# Input_Protection.net
KiCad netlist of a schematic drawn in Altium Designer
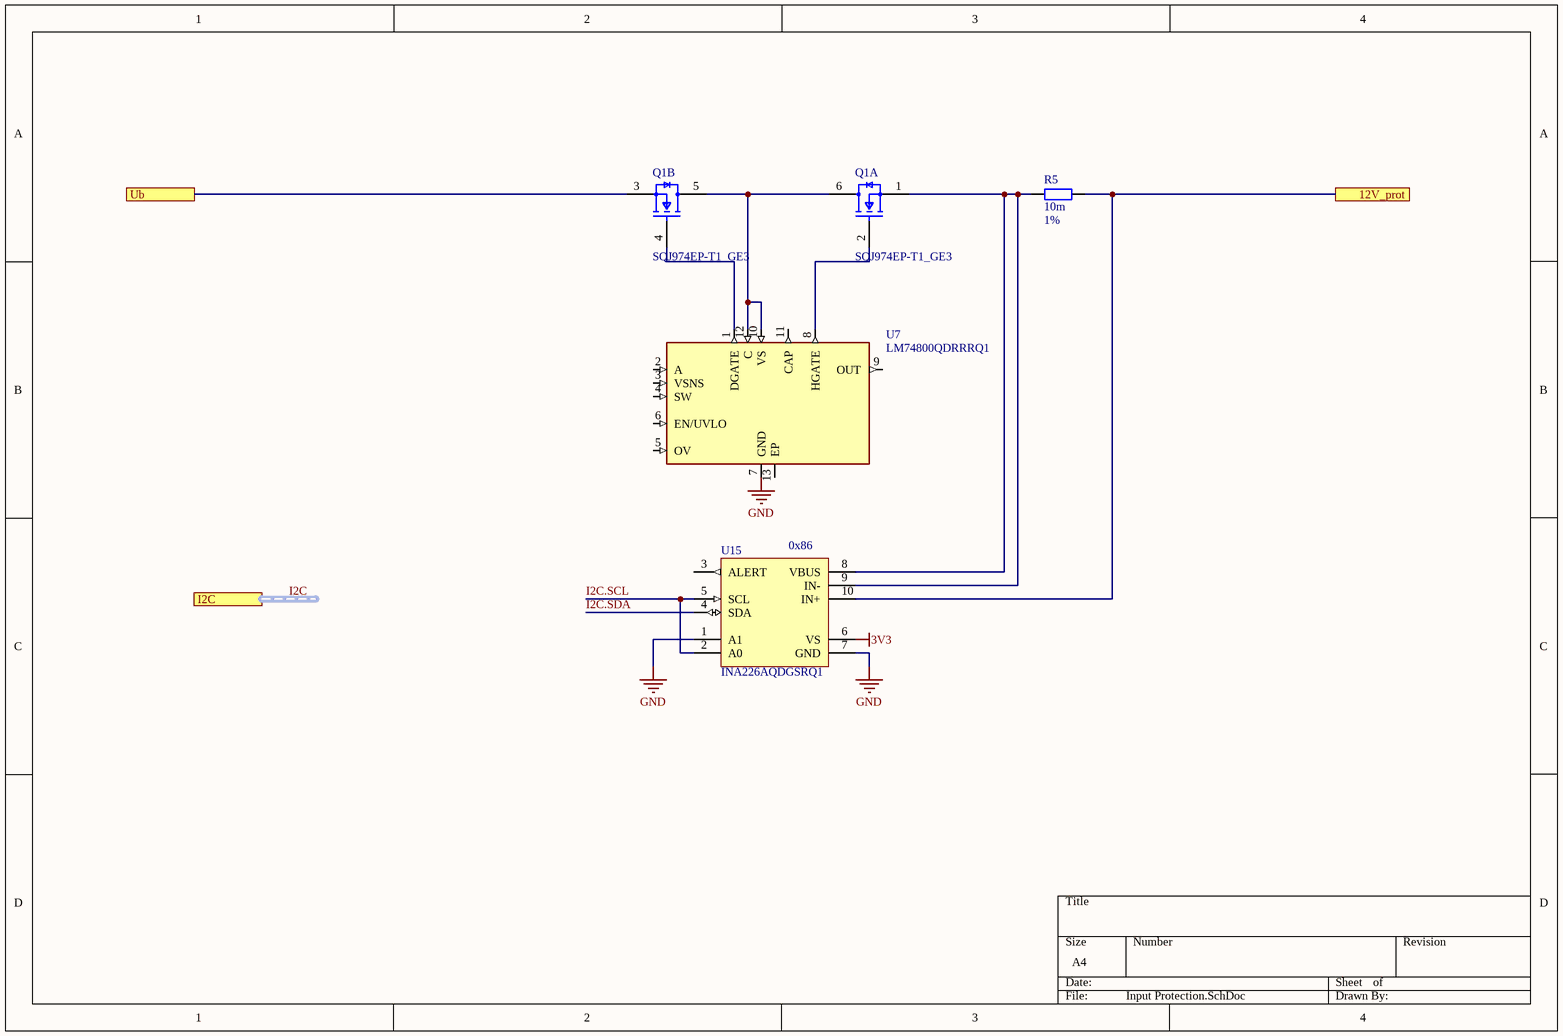
[diagram p0: Input Protection.SchDoc]

(export (version "E")
  (design (tool "Eeschema 10.0.6"))
  (components
    (comp (ref "Q1")
      (value "SQJ974EP-T1_GE3")
      (footprint "FP-C21-1498-DUAL-MFG")
      (description "Mosfet, N-Ch, 100V, 30A, 175Deg C, 48W Rohs Compliant: Yes")
      (libsource (lib "AFR365") (part "5deffecaf602b7dd3f7dff39dca0275"))
    )
    (comp (ref "R5")
      (value "10m")
      (footprint "SMD_1206_RES")
      (description "RES SMD 0.01 OHM 1% 1 1206 ±200ppm/°C")
      (fields
        (field (name "TOLERANCE") "1%")
        (field (name "POWER") "1W")
        (field (name "Comment") "ERJ-8BWFR010V")
      )
      (libsource (lib "AFR365") (part "resistor"))
    )
    (comp (ref "U7")
      (value "LM74800QDRRRQ1")
      (footprint "FP-DRR0012E-IPC_B")
      (description "AUTOMOTIVE IDEAL DIODE CONTROLLE OR Controller N+1 ORing Controller N-Channel 1: 1 12-WSON (3x3)")
      (libsource (lib "AFR365") (part "LM748x"))
    )
    (comp (ref "U15")
      (value "INA226AQDGSRQ1")
      (footprint "TI-DGS0010A-VSSOP-10")
      (description "SP Amp Current Shunt and Power Monitor Dual 5.5V 10-Pin VSSOP T/R")
      (libsource (lib "AFR365") (part "INA228"))
    )
  )
  (nets
    (net (code "2") (name "/12V_prot") (class "Default")
      (node (ref "R5") (pin "2") (pinfunction "2_2") (pintype "passive"))
      (node (ref "U15") (pin "10") (pinfunction "IN+_10") (pintype "power_in"))
    )
    (net (code "3") (name "/I2C.SCL") (class "Default")
      (node (ref "U15") (pin "2") (pinfunction "A0_2") (pintype "passive"))
      (node (ref "U15") (pin "5") (pinfunction "SCL_5") (pintype "input"))
    )
    (net (code "4") (name "/I2C.SDA") (class "Default")
      (node (ref "U15") (pin "4") (pinfunction "SDA_4") (pintype "bidirectional"))
    )
    (net (code "5") (name "/Ub") (class "Default")
      (node (ref "Q1") (pin "3") (pinfunction "S2_3") (pintype "passive"))
    )
    (net (code "7") (name "3V3") (class "Default")
      (node (ref "U15") (pin "6") (pinfunction "VS_6") (pintype "power_in"))
    )
    (net (code "8") (name "GND") (class "Default")
      (node (ref "U15") (pin "1") (pinfunction "A1_1") (pintype "passive"))
      (node (ref "U15") (pin "7") (pinfunction "GND_7") (pintype "power_in"))
      (node (ref "U7") (pin "7") (pinfunction "GND_7") (pintype "power_in"))
    )
    (net (code "9") (name "Net-(Q1A-D1)") (class "Default")
      (node (ref "Q1") (pin "5") (pinfunction "D2_5") (pintype "passive"))
      (node (ref "Q1") (pin "6") (pinfunction "D1_6") (pintype "passive"))
      (node (ref "U7") (pin "10") (pinfunction "VS_10") (pintype "input"))
      (node (ref "U7") (pin "12") (pinfunction "C_12") (pintype "input"))
    )
    (net (code "10") (name "Net-(Q1A-G1)") (class "Default")
      (node (ref "Q1") (pin "2") (pinfunction "G1_2") (pintype "passive"))
      (node (ref "U7") (pin "8") (pinfunction "HGATE_8") (pintype "output"))
    )
    (net (code "11") (name "Net-(Q1A-S1)") (class "Default")
      (node (ref "Q1") (pin "1") (pinfunction "S1_1") (pintype "passive"))
      (node (ref "R5") (pin "1") (pinfunction "1_1") (pintype "passive"))
      (node (ref "U15") (pin "8") (pinfunction "VBUS_8") (pintype "power_in"))
      (node (ref "U15") (pin "9") (pinfunction "IN-_9") (pintype "power_in"))
    )
    (net (code "12") (name "Net-(Q1B-G2)") (class "Default")
      (node (ref "Q1") (pin "4") (pinfunction "G2_4") (pintype "passive"))
      (node (ref "U7") (pin "1") (pinfunction "DGATE_1") (pintype "output"))
    )
    (net (code "13") (name "unconnected-(U7-A-Pad2)") (class "Default")
      (node (ref "U7") (pin "2") (pinfunction "A_2") (pintype "input"))
    )
    (net (code "14") (name "unconnected-(U7-CAP-Pad11)") (class "Default")
      (node (ref "U7") (pin "11") (pinfunction "CAP_11") (pintype "output"))
    )
    (net (code "15") (name "unconnected-(U7-EN{slash}UVLO-Pad6)") (class "Default")
      (node (ref "U7") (pin "6") (pinfunction "EN/UVLO_6") (pintype "input"))
    )
    (net (code "16") (name "unconnected-(U7-EP-Pad13)") (class "Default")
      (node (ref "U7") (pin "13") (pinfunction "EP_13") (pintype "power_in"))
    )
    (net (code "17") (name "unconnected-(U7-OUT-Pad9)") (class "Default")
      (node (ref "U7") (pin "9") (pinfunction "OUT_9") (pintype "output"))
    )
    (net (code "18") (name "unconnected-(U7-OV-Pad5)") (class "Default")
      (node (ref "U7") (pin "5") (pinfunction "OV_5") (pintype "input"))
    )
    (net (code "19") (name "unconnected-(U7-SW-Pad4)") (class "Default")
      (node (ref "U7") (pin "4") (pinfunction "SW_4") (pintype "input"))
    )
    (net (code "20") (name "unconnected-(U7-VSNS-Pad3)") (class "Default")
      (node (ref "U7") (pin "3") (pinfunction "VSNS_3") (pintype "input"))
    )
    (net (code "21") (name "unconnected-(U15-ALERT-Pad3)") (class "Default")
      (node (ref "U15") (pin "3") (pinfunction "ALERT_3") (pintype "output"))
    )
  )
)
